# supply.net
KiCad netlist of a schematic drawn in EAGLE
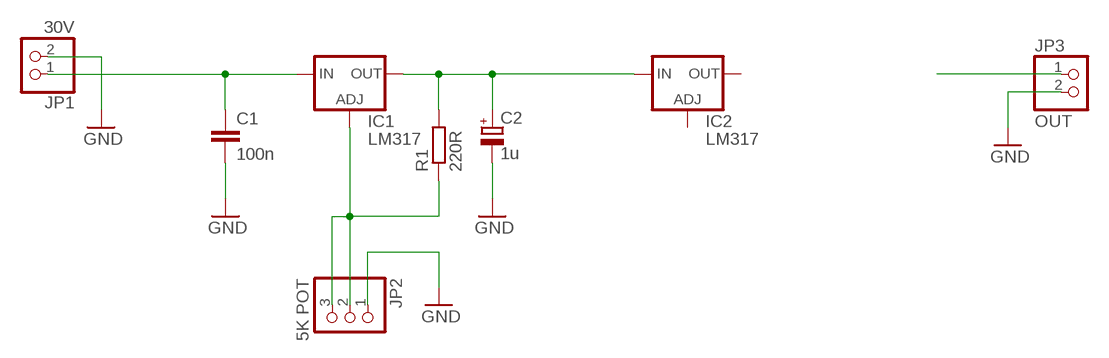
[diagram p0: schematic, sheet 1]

(export (version "E")
  (design (tool "Eeschema 10.0.6"))
  (components
    (comp (ref "C1")
      (value "100n")
      (footprint "eagle-import:C050-024X044")
      (libsource (lib "eagle-import") (part "C-EU050-024X044"))
    )
    (comp (ref "C2")
      (value "1u")
      (footprint "eagle-import:E2-5")
      (libsource (lib "eagle-import") (part "CPOL-EUE2-5"))
    )
    (comp (ref "IC1")
      (value "LM317")
      (footprint "eagle-import:317TS")
      (libsource (lib "eagle-import") (part "LM317TS"))
    )
    (comp (ref "IC2")
      (value "LM317")
      (footprint "eagle-import:317TS")
      (libsource (lib "eagle-import") (part "LM317TS"))
    )
    (comp (ref "JP1")
      (value "30V")
      (footprint "eagle-import:1X02")
      (libsource (lib "eagle-import") (part "PINHD-1X2"))
    )
    (comp (ref "JP2")
      (value "5K POT")
      (footprint "eagle-import:1X03")
      (libsource (lib "eagle-import") (part "PINHD-1X3"))
    )
    (comp (ref "JP3")
      (value "OUT")
      (footprint "eagle-import:1X02")
      (libsource (lib "eagle-import") (part "PINHD-1X2"))
    )
    (comp (ref "R1")
      (value "220R")
      (footprint "eagle-import:0204_5")
      (libsource (lib "eagle-import") (part "R-EU_0204/5"))
    )
  )
  (nets
    (net (code "1") (name "GND") (class "Default")
      (node (ref "C1") (pin "2") (pinfunction "2_2") (pintype "passive"))
      (node (ref "C2") (pin "-") (pinfunction "-_-") (pintype "passive"))
      (node (ref "JP1") (pin "2") (pinfunction "2_2") (pintype "passive"))
      (node (ref "JP2") (pin "1") (pinfunction "1_1") (pintype "passive"))
      (node (ref "JP3") (pin "2") (pinfunction "2_2") (pintype "passive"))
    )
    (net (code "2") (name "Net-(IC1-ADJ)") (class "Default")
      (node (ref "IC1") (pin "1") (pinfunction "ADJ_1") (pintype "input"))
      (node (ref "JP2") (pin "2") (pinfunction "2_2") (pintype "passive"))
      (node (ref "JP2") (pin "3") (pinfunction "3_3") (pintype "passive"))
      (node (ref "R1") (pin "1") (pinfunction "1_1") (pintype "passive"))
    )
    (net (code "3") (name "Net-(IC1-IN)") (class "Default")
      (node (ref "C1") (pin "1") (pinfunction "1_1") (pintype "passive"))
      (node (ref "IC1") (pin "3") (pinfunction "IN_3") (pintype "input"))
      (node (ref "JP1") (pin "1") (pinfunction "1_1") (pintype "passive"))
    )
    (net (code "4") (name "Net-(IC1-OUT)") (class "Default")
      (node (ref "C2") (pin "+") (pinfunction "+_+") (pintype "passive"))
      (node (ref "IC1") (pin "2") (pinfunction "OUT_2") (pintype "passive"))
      (node (ref "IC2") (pin "3") (pinfunction "IN_3") (pintype "input"))
      (node (ref "R1") (pin "2") (pinfunction "2_2") (pintype "passive"))
    )
    (net (code "5") (name "unconnected-(IC2-ADJ-Pad1)") (class "Default")
      (node (ref "IC2") (pin "1") (pinfunction "ADJ_1") (pintype "input"))
    )
    (net (code "6") (name "unconnected-(IC2-OUT-Pad2)") (class "Default")
      (node (ref "IC2") (pin "2") (pinfunction "OUT_2") (pintype "passive"))
    )
    (net (code "7") (name "unconnected-(JP3-Pad1)") (class "Default")
      (node (ref "JP3") (pin "1") (pinfunction "1_1") (pintype "passive"))
    )
  )
)
